# miniecu.net
KiCad netlist of a schematic drawn in EAGLE
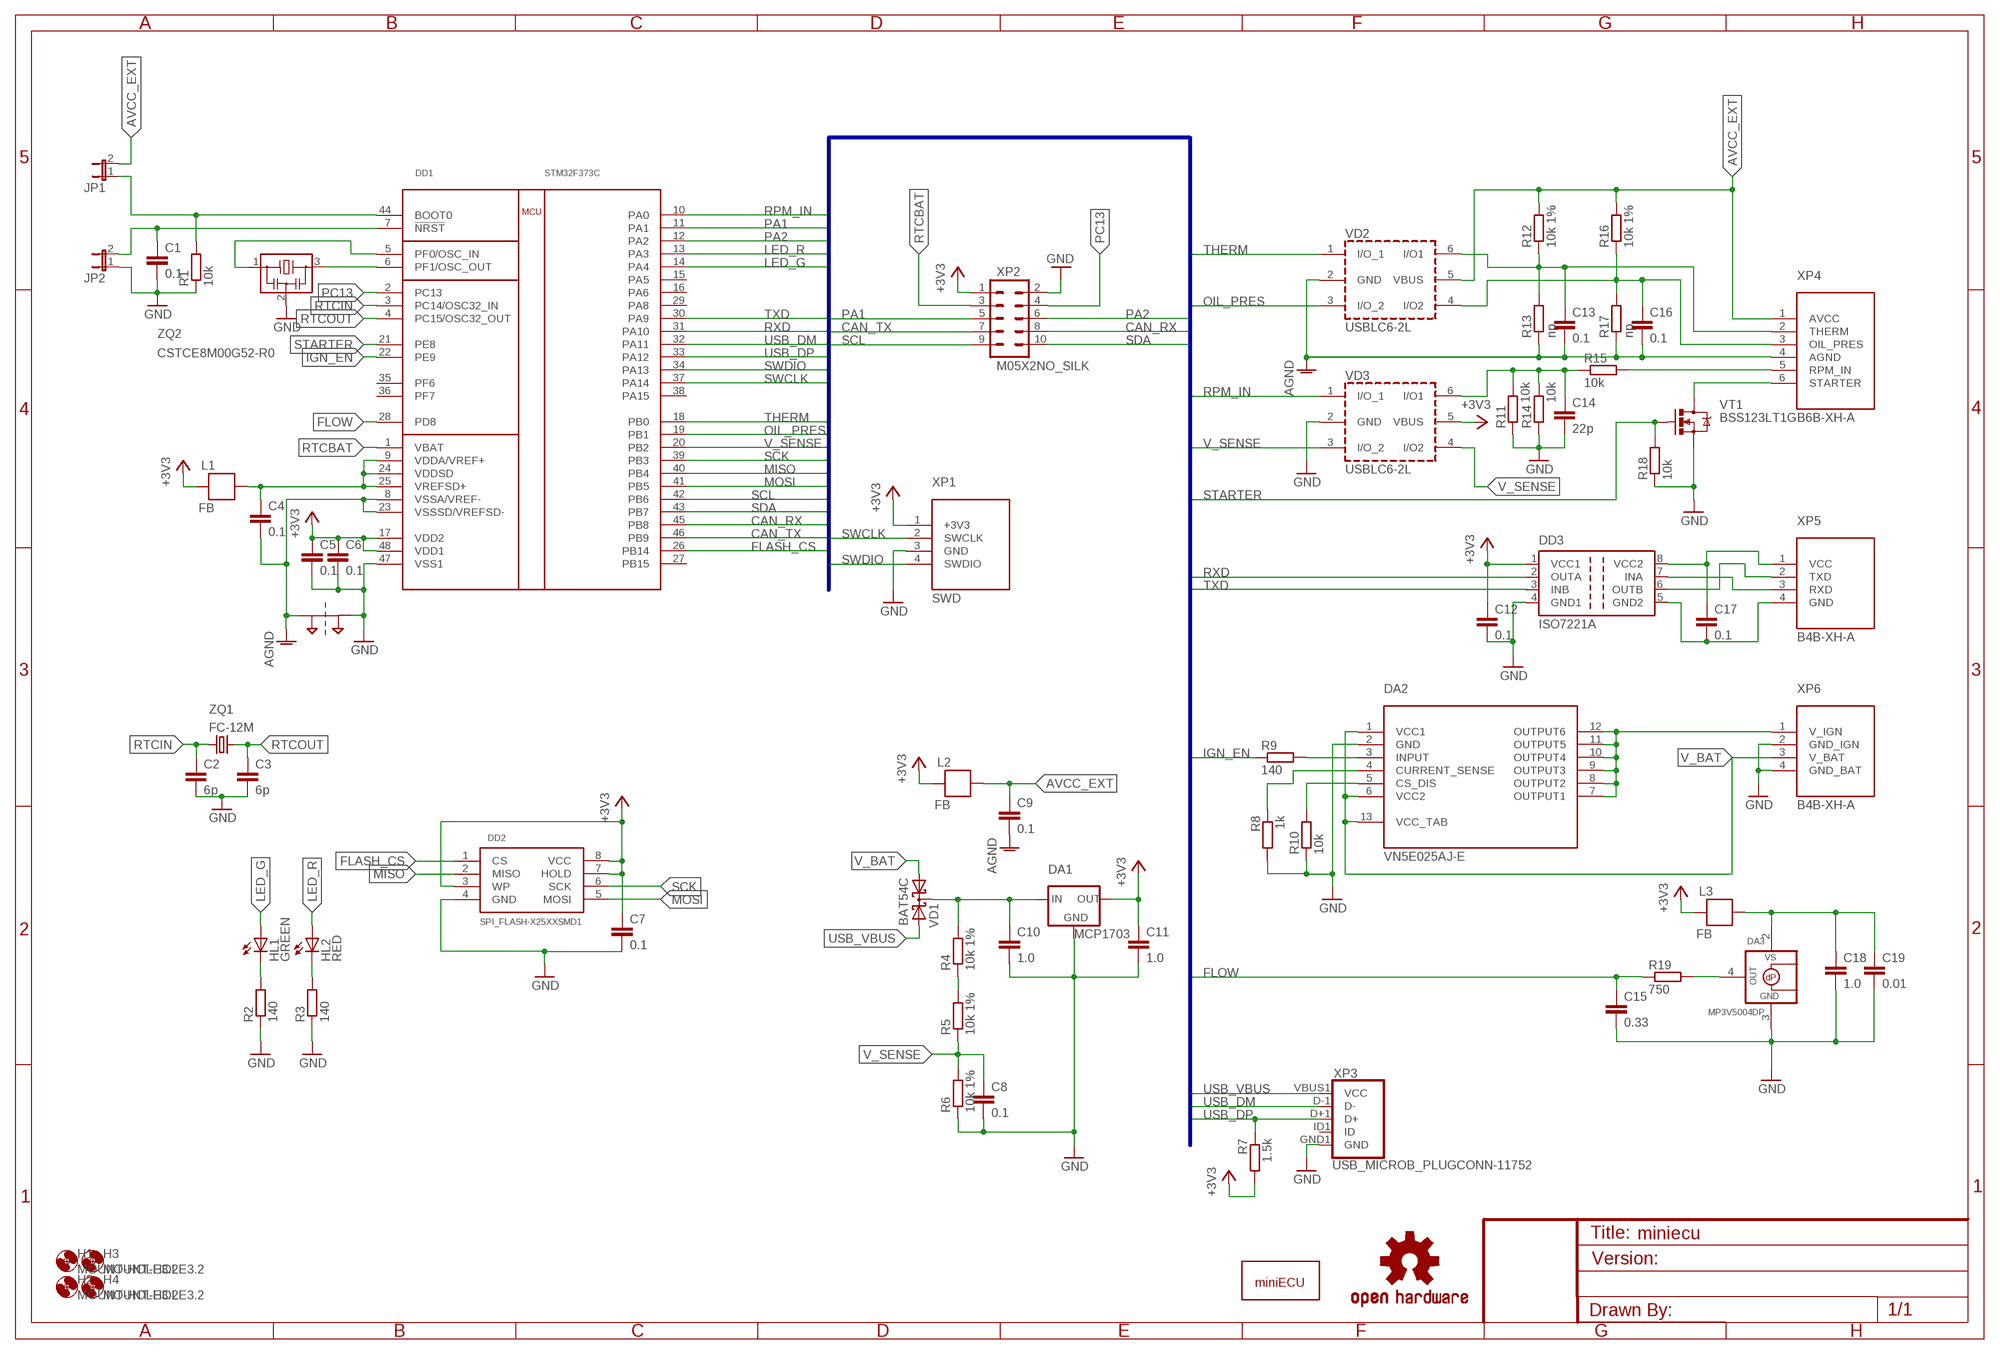
[diagram p0: schematic, sheet 1]

(export (version "E")
  (design (tool "Eeschema 10.0.6"))
  (components
    (comp (ref "C1")
      (value "0.1")
      (footprint "eagle-import:C0603")
      (libsource (lib "eagle-import") (part "C-EUC0603"))
    )
    (comp (ref "C2")
      (value "6p")
      (footprint "eagle-import:C0603")
      (libsource (lib "eagle-import") (part "C-EUC0603"))
    )
    (comp (ref "C3")
      (value "6p")
      (footprint "eagle-import:C0603")
      (libsource (lib "eagle-import") (part "C-EUC0603"))
    )
    (comp (ref "C4")
      (value "0.1")
      (footprint "eagle-import:C0603")
      (libsource (lib "eagle-import") (part "C-EUC0603"))
    )
    (comp (ref "C5")
      (value "0.1")
      (footprint "eagle-import:C0603")
      (libsource (lib "eagle-import") (part "C-EUC0603"))
    )
    (comp (ref "C6")
      (value "0.1")
      (footprint "eagle-import:C0603")
      (libsource (lib "eagle-import") (part "C-EUC0603"))
    )
    (comp (ref "C7")
      (value "0.1")
      (footprint "eagle-import:C0603")
      (libsource (lib "eagle-import") (part "C-EUC0603"))
    )
    (comp (ref "C8")
      (value "0.1")
      (footprint "eagle-import:C0603")
      (libsource (lib "eagle-import") (part "C-EUC0603"))
    )
    (comp (ref "C9")
      (value "0.1")
      (footprint "eagle-import:C0603")
      (libsource (lib "eagle-import") (part "C-EUC0603"))
    )
    (comp (ref "C10")
      (value "1.0")
      (footprint "eagle-import:C0805")
      (libsource (lib "eagle-import") (part "C-EUC0805"))
    )
    (comp (ref "C11")
      (value "1.0")
      (footprint "eagle-import:C0805")
      (libsource (lib "eagle-import") (part "C-EUC0805"))
    )
    (comp (ref "C12")
      (value "0.1")
      (footprint "eagle-import:C0603")
      (libsource (lib "eagle-import") (part "C-EUC0603"))
    )
    (comp (ref "C13")
      (value "0.1")
      (footprint "eagle-import:C0603")
      (libsource (lib "eagle-import") (part "C-EUC0603"))
    )
    (comp (ref "C14")
      (value "22p")
      (footprint "eagle-import:C0603")
      (libsource (lib "eagle-import") (part "C-EUC0603"))
    )
    (comp (ref "C15")
      (value "0.33")
      (footprint "eagle-import:C0603")
      (libsource (lib "eagle-import") (part "C-EUC0603"))
    )
    (comp (ref "C16")
      (value "0.1")
      (footprint "eagle-import:C0603")
      (libsource (lib "eagle-import") (part "C-EUC0603"))
    )
    (comp (ref "C17")
      (value "0.1")
      (footprint "eagle-import:C0603")
      (libsource (lib "eagle-import") (part "C-EUC0603"))
    )
    (comp (ref "C18")
      (value "1.0")
      (footprint "eagle-import:C0805")
      (libsource (lib "eagle-import") (part "C-EUC0805"))
    )
    (comp (ref "C19")
      (value "0.01")
      (footprint "eagle-import:C0603")
      (libsource (lib "eagle-import") (part "C-EUC0603"))
    )
    (comp (ref "DA1")
      (value "MCP1703")
      (footprint "eagle-import:SOT23")
      (libsource (lib "eagle-import") (part "MCP1700SOT-23"))
    )
    (comp (ref "DA2")
      (value "VN5E025AJ-E")
      (footprint "eagle-import:POWERSSO-12")
      (libsource (lib "eagle-import") (part "VN5E025AJ-E"))
    )
    (comp (ref "DA3")
      (value "MP3V5004DP")
      (footprint "eagle-import:SOP8-1351")
      (libsource (lib "eagle-import") (part "MPXV7025DP"))
    )
    (comp (ref "DD1")
      (value "STM32F373C")
      (footprint "eagle-import:LQFP48")
      (libsource (lib "eagle-import") (part "STM32F373C"))
    )
    (comp (ref "DD2")
      (value "SPI_FLASH-X25XXSMD1")
      (footprint "eagle-import:SO08-EIAJ")
      (libsource (lib "eagle-import") (part "SPI_FLASH-X25XXSMD1"))
    )
    (comp (ref "DD3")
      (value "ISO7221A")
      (footprint "eagle-import:SO-08")
      (fields (field (name "MPN") "ISO7221AD"))
      (libsource (lib "eagle-import") (part "ISO7221A"))
    )
    (comp (ref "H1")
      (value "MOUNT-HOLE3.2")
      (footprint "eagle-import:3,2")
      (libsource (lib "eagle-import") (part "MOUNT-HOLE3.2"))
    )
    (comp (ref "H2")
      (value "MOUNT-HOLE3.2")
      (footprint "eagle-import:3,2")
      (libsource (lib "eagle-import") (part "MOUNT-HOLE3.2"))
    )
    (comp (ref "H3")
      (value "MOUNT-HOLE3.2")
      (footprint "eagle-import:3,2")
      (libsource (lib "eagle-import") (part "MOUNT-HOLE3.2"))
    )
    (comp (ref "H4")
      (value "MOUNT-HOLE3.2")
      (footprint "eagle-import:3,2")
      (libsource (lib "eagle-import") (part "MOUNT-HOLE3.2"))
    )
    (comp (ref "HL1")
      (value "GREEN")
      (footprint "eagle-import:LED-0603")
      (libsource (lib "eagle-import") (part "LED-GREEN0603"))
    )
    (comp (ref "HL2")
      (value "RED")
      (footprint "eagle-import:LED-0603")
      (libsource (lib "eagle-import") (part "LED-RED0603"))
    )
    (comp (ref "JP1")
      (value "JUMPER-2SMD-NO")
      (footprint "eagle-import:SJ_2S-NO")
      (libsource (lib "eagle-import") (part "JUMPER-2SMD-NO"))
    )
    (comp (ref "JP2")
      (value "JUMPER-2SMD-NO")
      (footprint "eagle-import:SJ_2S-NO")
      (libsource (lib "eagle-import") (part "JUMPER-2SMD-NO"))
    )
    (comp (ref "L1")
      (value "FB")
      (footprint "eagle-import:0603")
      (libsource (lib "eagle-import") (part "FB"))
    )
    (comp (ref "L2")
      (value "FB")
      (footprint "eagle-import:0603")
      (libsource (lib "eagle-import") (part "FB"))
    )
    (comp (ref "L3")
      (value "FB")
      (footprint "eagle-import:0603")
      (libsource (lib "eagle-import") (part "FB"))
    )
    (comp (ref "LOGO1")
      (value "MINIECU_LOGO")
      (footprint "eagle-import:MINIECU_LOGO")
      (libsource (lib "eagle-import") (part "MINIECU_LOGO"))
    )
    (comp (ref "LOGO2")
      (value "OSHW-LOGOL")
      (footprint "eagle-import:OSHW-LOGO-L")
      (libsource (lib "eagle-import") (part "OSHW-LOGOL"))
    )
    (comp (ref "PT1")
      (value "2PT_GND_TIE")
      (footprint "eagle-import:2PT_GND_TIE")
      (libsource (lib "eagle-import") (part "2PT_GND_TIE"))
    )
    (comp (ref "R1")
      (value "10k")
      (footprint "eagle-import:R0603")
      (libsource (lib "eagle-import") (part "R-EU_R0603"))
    )
    (comp (ref "R2")
      (value "140")
      (footprint "eagle-import:R0603")
      (libsource (lib "eagle-import") (part "R-EU_R0603"))
    )
    (comp (ref "R3")
      (value "140")
      (footprint "eagle-import:R0603")
      (libsource (lib "eagle-import") (part "R-EU_R0603"))
    )
    (comp (ref "R4")
      (value "10k 1%")
      (footprint "eagle-import:R0805")
      (libsource (lib "eagle-import") (part "R-EU_R0805"))
    )
    (comp (ref "R5")
      (value "10k 1%")
      (footprint "eagle-import:R0805")
      (libsource (lib "eagle-import") (part "R-EU_R0805"))
    )
    (comp (ref "R6")
      (value "10k 1%")
      (footprint "eagle-import:R0805")
      (libsource (lib "eagle-import") (part "R-EU_R0805"))
    )
    (comp (ref "R7")
      (value "1.5k")
      (footprint "eagle-import:R0603")
      (libsource (lib "eagle-import") (part "R-EU_R0603"))
    )
    (comp (ref "R8")
      (value "1k")
      (footprint "eagle-import:R0603")
      (libsource (lib "eagle-import") (part "R-EU_R0603"))
    )
    (comp (ref "R9")
      (value "140")
      (footprint "eagle-import:R0603")
      (libsource (lib "eagle-import") (part "R-EU_R0603"))
    )
    (comp (ref "R10")
      (value "10k")
      (footprint "eagle-import:R0603")
      (libsource (lib "eagle-import") (part "R-EU_R0603"))
    )
    (comp (ref "R11")
      (value "10k")
      (footprint "eagle-import:R0603")
      (libsource (lib "eagle-import") (part "R-EU_R0603"))
    )
    (comp (ref "R12")
      (value "10k 1%")
      (footprint "eagle-import:R0805")
      (libsource (lib "eagle-import") (part "R-EU_R0805"))
    )
    (comp (ref "R13")
      (value "np")
      (footprint "eagle-import:R0805")
      (libsource (lib "eagle-import") (part "R-EU_R0805"))
    )
    (comp (ref "R14")
      (value "10k")
      (footprint "eagle-import:R0603")
      (libsource (lib "eagle-import") (part "R-EU_R0603"))
    )
    (comp (ref "R15")
      (value "10k")
      (footprint "eagle-import:R0603")
      (libsource (lib "eagle-import") (part "R-EU_R0603"))
    )
    (comp (ref "R16")
      (value "10k 1%")
      (footprint "eagle-import:R0805")
      (libsource (lib "eagle-import") (part "R-EU_R0805"))
    )
    (comp (ref "R17")
      (value "np")
      (footprint "eagle-import:R0805")
      (libsource (lib "eagle-import") (part "R-EU_R0805"))
    )
    (comp (ref "R18")
      (value "10k")
      (footprint "eagle-import:R0603")
      (libsource (lib "eagle-import") (part "R-EU_R0603"))
    )
    (comp (ref "R19")
      (value "750")
      (footprint "eagle-import:R0603")
      (libsource (lib "eagle-import") (part "R-EU_R0603"))
    )
    (comp (ref "VD1")
      (value "BAT54C")
      (footprint "eagle-import:SOT23")
      (libsource (lib "eagle-import") (part "BAT54C"))
    )
    (comp (ref "VD2")
      (value "USBLC6-2L")
      (footprint "eagle-import:SOT-23-6L")
      (libsource (lib "eagle-import") (part "USBLC6-2SC6"))
    )
    (comp (ref "VD3")
      (value "USBLC6-2L")
      (footprint "eagle-import:SOT-23-6L")
      (libsource (lib "eagle-import") (part "USBLC6-2SC6"))
    )
    (comp (ref "VT1")
      (value "BSS123LT1G")
      (footprint "eagle-import:SOT23")
      (libsource (lib "eagle-import") (part "MOSFET-NCHANNELBSS123LT1G"))
    )
    (comp (ref "XP1")
      (value "SWD")
      (footprint "eagle-import:1X04-1.27MM")
      (libsource (lib "eagle-import") (part "SWD"))
    )
    (comp (ref "XP2")
      (value "M05X2NO_SILK")
      (footprint "eagle-import:2X5_NOSILK")
      (libsource (lib "eagle-import") (part "M05X2NO_SILK"))
    )
    (comp (ref "XP3")
      (value "USB_MICROB_PLUGCONN-11752")
      (footprint "eagle-import:USB-B-MICRO-SMD_V03")
      (libsource (lib "eagle-import") (part "USB_MICROB_PLUGCONN-11752"))
    )
    (comp (ref "XP4")
      (value "B6B-XH-A")
      (footprint "eagle-import:B6B-XH")
      (libsource (lib "eagle-import") (part "SENSORS-B6B-XH-A"))
    )
    (comp (ref "XP5")
      (value "B4B-XH-A")
      (footprint "eagle-import:B4B-XH")
      (libsource (lib "eagle-import") (part "UART-B4B-XH-A"))
    )
    (comp (ref "XP6")
      (value "B4B-XH-A")
      (footprint "eagle-import:B4B-XH")
      (libsource (lib "eagle-import") (part "IGN_POWER-B4B-XH-A"))
    )
    (comp (ref "ZQ1")
      (value "FC-12M")
      (footprint "eagle-import:FC-12M")
      (libsource (lib "eagle-import") (part "FC-12M"))
    )
    (comp (ref "ZQ2")
      (value "CSTCE8M00G52-R0")
      (footprint "eagle-import:CSTCE")
      (libsource (lib "eagle-import") (part "CSTC?E8M00G52-R0"))
    )
  )
  (nets
    (net (code "1") (name "+3V3") (class "Default")
      (node (ref "C11") (pin "1") (pinfunction "1_1") (pintype "passive"))
      (node (ref "C12") (pin "1") (pinfunction "1_1") (pintype "passive"))
      (node (ref "C5") (pin "1") (pinfunction "1_1") (pintype "passive"))
      (node (ref "C6") (pin "1") (pinfunction "1_1") (pintype "passive"))
      (node (ref "C7") (pin "1") (pinfunction "1_1") (pintype "passive"))
      (node (ref "DA1") (pin "2") (pinfunction "OUT_2") (pintype "passive"))
      (node (ref "DD1") (pin "17") (pinfunction "VDD2_17") (pintype "power_in"))
      (node (ref "DD1") (pin "48") (pinfunction "VDD1_48") (pintype "power_in"))
      (node (ref "DD2") (pin "3") (pinfunction "WP_3") (pintype "bidirectional"))
      (node (ref "DD2") (pin "7") (pinfunction "HOLD_7") (pintype "bidirectional"))
      (node (ref "DD2") (pin "8") (pinfunction "VCC_8") (pintype "bidirectional"))
      (node (ref "DD3") (pin "1") (pinfunction "VCC1_1") (pintype "power_in"))
      (node (ref "L1") (pin "2") (pinfunction "P$2_2") (pintype "bidirectional"))
      (node (ref "L2") (pin "2") (pinfunction "P$2_2") (pintype "bidirectional"))
      (node (ref "L3") (pin "2") (pinfunction "P$2_2") (pintype "bidirectional"))
      (node (ref "R7") (pin "2") (pinfunction "2_2") (pintype "passive"))
      (node (ref "VD3") (pin "5") (pinfunction "VBUS_5") (pintype "bidirectional"))
      (node (ref "XP1") (pin "1") (pinfunction "+3V3_1") (pintype "power_in"))
      (node (ref "XP2") (pin "1") (pinfunction "1_1") (pintype "passive"))
    )
    (net (code "2") (name "/CAN_RX") (class "Default")
      (node (ref "DD1") (pin "45") (pinfunction "PB8_45") (pintype "bidirectional"))
      (node (ref "XP2") (pin "8") (pinfunction "8_8") (pintype "passive"))
    )
    (net (code "3") (name "/CAN_TX") (class "Default")
      (node (ref "DD1") (pin "46") (pinfunction "PB9_46") (pintype "bidirectional"))
      (node (ref "XP2") (pin "7") (pinfunction "7_7") (pintype "passive"))
    )
    (net (code "4") (name "/OIL_PRES") (class "Default")
      (node (ref "C16") (pin "1") (pinfunction "1_1") (pintype "passive"))
      (node (ref "DD1") (pin "19") (pinfunction "PB1_19") (pintype "bidirectional"))
      (node (ref "R16") (pin "1") (pinfunction "1_1") (pintype "passive"))
      (node (ref "R17") (pin "2") (pinfunction "2_2") (pintype "passive"))
      (node (ref "VD2") (pin "3") (pinfunction "I/O_2_3") (pintype "bidirectional"))
      (node (ref "VD2") (pin "4") (pinfunction "I/O2_4") (pintype "bidirectional"))
      (node (ref "XP4") (pin "3") (pinfunction "OIL_PRES_3") (pintype "passive"))
    )
    (net (code "5") (name "/PA1") (class "Default")
      (node (ref "DD1") (pin "11") (pinfunction "PA1_11") (pintype "bidirectional"))
      (node (ref "XP2") (pin "5") (pinfunction "5_5") (pintype "passive"))
    )
    (net (code "6") (name "/PA2") (class "Default")
      (node (ref "DD1") (pin "12") (pinfunction "PA2_12") (pintype "bidirectional"))
      (node (ref "XP2") (pin "6") (pinfunction "6_6") (pintype "passive"))
    )
    (net (code "7") (name "/RPM_IN") (class "Default")
      (node (ref "C14") (pin "1") (pinfunction "1_1") (pintype "passive"))
      (node (ref "DD1") (pin "10") (pinfunction "PA0_10") (pintype "bidirectional"))
      (node (ref "R11") (pin "2") (pinfunction "2_2") (pintype "passive"))
      (node (ref "R14") (pin "2") (pinfunction "2_2") (pintype "passive"))
      (node (ref "R15") (pin "1") (pinfunction "1_1") (pintype "passive"))
      (node (ref "VD3") (pin "1") (pinfunction "I/O_1_1") (pintype "bidirectional"))
      (node (ref "VD3") (pin "6") (pinfunction "I/O1_6") (pintype "bidirectional"))
    )
    (net (code "8") (name "/RXD") (class "Default")
      (node (ref "DD1") (pin "31") (pinfunction "PA10_31") (pintype "bidirectional"))
      (node (ref "DD3") (pin "2") (pinfunction "OUTA_2") (pintype "output"))
    )
    (net (code "9") (name "/SCL") (class "Default")
      (node (ref "DD1") (pin "42") (pinfunction "PB6_42") (pintype "bidirectional"))
      (node (ref "XP2") (pin "9") (pinfunction "9_9") (pintype "passive"))
    )
    (net (code "10") (name "/SDA") (class "Default")
      (node (ref "DD1") (pin "43") (pinfunction "PB7_43") (pintype "bidirectional"))
      (node (ref "XP2") (pin "10") (pinfunction "10_10") (pintype "passive"))
    )
    (net (code "11") (name "/SWCLK") (class "Default")
      (node (ref "DD1") (pin "37") (pinfunction "PA14_37") (pintype "bidirectional"))
      (node (ref "XP1") (pin "2") (pinfunction "SWCLK_2") (pintype "bidirectional"))
    )
    (net (code "12") (name "/SWDIO") (class "Default")
      (node (ref "DD1") (pin "34") (pinfunction "PA13_34") (pintype "bidirectional"))
      (node (ref "XP1") (pin "4") (pinfunction "SWDIO_4") (pintype "bidirectional"))
    )
    (net (code "13") (name "/THERM") (class "Default")
      (node (ref "C13") (pin "1") (pinfunction "1_1") (pintype "passive"))
      (node (ref "DD1") (pin "18") (pinfunction "PB0_18") (pintype "bidirectional"))
      (node (ref "R12") (pin "1") (pinfunction "1_1") (pintype "passive"))
      (node (ref "R13") (pin "2") (pinfunction "2_2") (pintype "passive"))
      (node (ref "VD2") (pin "1") (pinfunction "I/O_1_1") (pintype "bidirectional"))
      (node (ref "VD2") (pin "6") (pinfunction "I/O1_6") (pintype "bidirectional"))
      (node (ref "XP4") (pin "2") (pinfunction "THERM_2") (pintype "passive"))
    )
    (net (code "14") (name "/TXD") (class "Default")
      (node (ref "DD1") (pin "30") (pinfunction "PA9_30") (pintype "bidirectional"))
      (node (ref "DD3") (pin "3") (pinfunction "INB_3") (pintype "input"))
    )
    (net (code "15") (name "/USB_DM") (class "Default")
      (node (ref "DD1") (pin "32") (pinfunction "PA11_32") (pintype "bidirectional"))
      (node (ref "XP3") (pin "D-1") (pinfunction "D-_D-1") (pintype "bidirectional"))
    )
    (net (code "16") (name "/USB_DP") (class "Default")
      (node (ref "DD1") (pin "33") (pinfunction "PA12_33") (pintype "bidirectional"))
      (node (ref "R7") (pin "1") (pinfunction "1_1") (pintype "passive"))
      (node (ref "XP3") (pin "D+1") (pinfunction "D+_D+1") (pintype "bidirectional"))
    )
    (net (code "17") (name "AGND") (class "Default")
      (node (ref "C13") (pin "2") (pinfunction "2_2") (pintype "passive"))
      (node (ref "C16") (pin "2") (pinfunction "2_2") (pintype "passive"))
      (node (ref "C4") (pin "2") (pinfunction "2_2") (pintype "passive"))
      (node (ref "C9") (pin "2") (pinfunction "2_2") (pintype "passive"))
      (node (ref "DD1") (pin "23") (pinfunction "VSSSD/VREFSD-_23") (pintype "power_in"))
      (node (ref "DD1") (pin "8") (pinfunction "VSSA/VREF-_8") (pintype "power_in"))
      (node (ref "PT1") (pin "P$1") (pinfunction "P$1_P$1") (pintype "bidirectional"))
      (node (ref "R13") (pin "1") (pinfunction "1_1") (pintype "passive"))
      (node (ref "R17") (pin "1") (pinfunction "1_1") (pintype "passive"))
      (node (ref "VD2") (pin "2") (pinfunction "GND_2") (pintype "bidirectional"))
      (node (ref "XP4") (pin "4") (pinfunction "AGND_4") (pintype "passive"))
    )
    (net (code "18") (name "AVCC_EXT") (class "Default")
      (node (ref "C9") (pin "1") (pinfunction "1_1") (pintype "passive"))
      (node (ref "JP1") (pin "2") (pinfunction "2_2") (pintype "passive"))
      (node (ref "L2") (pin "1") (pinfunction "P$1_1") (pintype "bidirectional"))
      (node (ref "R12") (pin "2") (pinfunction "2_2") (pintype "passive"))
      (node (ref "R16") (pin "2") (pinfunction "2_2") (pintype "passive"))
      (node (ref "VD2") (pin "5") (pinfunction "VBUS_5") (pintype "bidirectional"))
      (node (ref "XP4") (pin "1") (pinfunction "AVCC_1") (pintype "passive"))
    )
    (net (code "19") (name "FLASH_CS") (class "Default")
      (node (ref "DD1") (pin "26") (pinfunction "PB14_26") (pintype "bidirectional"))
      (node (ref "DD2") (pin "1") (pinfunction "CS_1") (pintype "bidirectional"))
    )
    (net (code "20") (name "FLOW") (class "Default")
      (node (ref "C15") (pin "1") (pinfunction "1_1") (pintype "passive"))
      (node (ref "DD1") (pin "28") (pinfunction "PD8_28") (pintype "bidirectional"))
      (node (ref "R19") (pin "1") (pinfunction "1_1") (pintype "passive"))
    )
    (net (code "21") (name "GND") (class "Default")
      (node (ref "C1") (pin "2") (pinfunction "2_2") (pintype "passive"))
      (node (ref "C10") (pin "2") (pinfunction "2_2") (pintype "passive"))
      (node (ref "C11") (pin "2") (pinfunction "2_2") (pintype "passive"))
      (node (ref "C12") (pin "2") (pinfunction "2_2") (pintype "passive"))
      (node (ref "C14") (pin "2") (pinfunction "2_2") (pintype "passive"))
      (node (ref "C15") (pin "2") (pinfunction "2_2") (pintype "passive"))
      (node (ref "C18") (pin "2") (pinfunction "2_2") (pintype "passive"))
      (node (ref "C19") (pin "2") (pinfunction "2_2") (pintype "passive"))
      (node (ref "C2") (pin "2") (pinfunction "2_2") (pintype "passive"))
      (node (ref "C3") (pin "2") (pinfunction "2_2") (pintype "passive"))
      (node (ref "C5") (pin "2") (pinfunction "2_2") (pintype "passive"))
      (node (ref "C6") (pin "2") (pinfunction "2_2") (pintype "passive"))
      (node (ref "C7") (pin "2") (pinfunction "2_2") (pintype "passive"))
      (node (ref "C8") (pin "2") (pinfunction "2_2") (pintype "passive"))
      (node (ref "DA1") (pin "1") (pinfunction "GND_1") (pintype "input"))
      (node (ref "DA2") (pin "2") (pinfunction "GND_2") (pintype "power_in"))
      (node (ref "DA3") (pin "3") (pinfunction "GND_3") (pintype "power_in"))
      (node (ref "DD1") (pin "47") (pinfunction "VSS1_47") (pintype "power_in"))
      (node (ref "DD2") (pin "4") (pinfunction "GND_4") (pintype "bidirectional"))
      (node (ref "DD3") (pin "4") (pinfunction "GND1_4") (pintype "power_in"))
      (node (ref "JP2") (pin "1") (pinfunction "1_1") (pintype "passive"))
      (node (ref "PT1") (pin "P$2") (pinfunction "P$2_P$2") (pintype "bidirectional"))
      (node (ref "R1") (pin "1") (pinfunction "1_1") (pintype "passive"))
      (node (ref "R10") (pin "1") (pinfunction "1_1") (pintype "passive"))
      (node (ref "R11") (pin "1") (pinfunction "1_1") (pintype "passive"))
      (node (ref "R14") (pin "1") (pinfunction "1_1") (pintype "passive"))
      (node (ref "R18") (pin "1") (pinfunction "1_1") (pintype "passive"))
      (node (ref "R2") (pin "1") (pinfunction "1_1") (pintype "passive"))
      (node (ref "R3") (pin "1") (pinfunction "1_1") (pintype "passive"))
      (node (ref "R6") (pin "1") (pinfunction "1_1") (pintype "passive"))
      (node (ref "R8") (pin "2") (pinfunction "2_2") (pintype "passive"))
      (node (ref "VD3") (pin "2") (pinfunction "GND_2") (pintype "bidirectional"))
      (node (ref "VT1") (pin "2") (pinfunction "S_2") (pintype "passive"))
      (node (ref "XP1") (pin "3") (pinfunction "GND_3") (pintype "power_in"))
      (node (ref "XP2") (pin "2") (pinfunction "2_2") (pintype "passive"))
      (node (ref "XP3") (pin "GND1") (pinfunction "GND_GND1") (pintype "bidirectional"))
      (node (ref "XP6") (pin "2") (pinfunction "GND_IGN_2") (pintype "passive"))
      (node (ref "XP6") (pin "4") (pinfunction "GND_BAT_4") (pintype "passive"))
      (node (ref "ZQ2") (pin "2") (pinfunction "2_2") (pintype "passive"))
    )
    (net (code "22") (name "IGN_EN") (class "Default")
      (node (ref "DD1") (pin "22") (pinfunction "PE9_22") (pintype "bidirectional"))
      (node (ref "R9") (pin "1") (pinfunction "1_1") (pintype "passive"))
    )
    (net (code "23") (name "LED_G") (class "Default")
      (node (ref "DD1") (pin "14") (pinfunction "PA4_14") (pintype "bidirectional"))
      (node (ref "HL1") (pin "A") (pinfunction "A_A") (pintype "passive"))
    )
    (net (code "24") (name "LED_R") (class "Default")
      (node (ref "DD1") (pin "13") (pinfunction "PA3_13") (pintype "bidirectional"))
      (node (ref "HL2") (pin "A") (pinfunction "A_A") (pintype "passive"))
    )
    (net (code "25") (name "MISO") (class "Default")
      (node (ref "DD1") (pin "40") (pinfunction "PB4_40") (pintype "bidirectional"))
      (node (ref "DD2") (pin "2") (pinfunction "MISO_2") (pintype "bidirectional"))
    )
    (net (code "26") (name "MOSI") (class "Default")
      (node (ref "DD1") (pin "41") (pinfunction "PB5_41") (pintype "bidirectional"))
      (node (ref "DD2") (pin "5") (pinfunction "MOSI_5") (pintype "bidirectional"))
    )
    (net (code "27") (name "Net-(DA1-IN)") (class "Default")
      (node (ref "C10") (pin "1") (pinfunction "1_1") (pintype "passive"))
      (node (ref "DA1") (pin "3") (pinfunction "IN_3") (pintype "input"))
      (node (ref "R4") (pin "2") (pinfunction "2_2") (pintype "passive"))
      (node (ref "VD1") (pin "3") (pinfunction "CC_3") (pintype "passive"))
    )
    (net (code "28") (name "Net-(DA2-CS_DIS)") (class "Default")
      (node (ref "DA2") (pin "5") (pinfunction "CS_DIS_5") (pintype "input"))
      (node (ref "R10") (pin "2") (pinfunction "2_2") (pintype "passive"))
    )
    (net (code "29") (name "Net-(DA2-CURRENT_SENSE)") (class "Default")
      (node (ref "DA2") (pin "4") (pinfunction "CURRENT_SENSE_4") (pintype "bidirectional"))
      (node (ref "R8") (pin "1") (pinfunction "1_1") (pintype "passive"))
    )
    (net (code "30") (name "Net-(DA2-INPUT)") (class "Default")
      (node (ref "DA2") (pin "3") (pinfunction "INPUT_3") (pintype "input"))
      (node (ref "R9") (pin "2") (pinfunction "2_2") (pintype "passive"))
    )
    (net (code "31") (name "Net-(DA2-OUTPUT1)") (class "Default")
      (node (ref "DA2") (pin "10") (pinfunction "OUTPUT4_10") (pintype "power_in"))
      (node (ref "DA2") (pin "11") (pinfunction "OUTPUT5_11") (pintype "power_in"))
      (node (ref "DA2") (pin "12") (pinfunction "OUTPUT6_12") (pintype "power_in"))
      (node (ref "DA2") (pin "7") (pinfunction "OUTPUT1_7") (pintype "power_in"))
      (node (ref "DA2") (pin "8") (pinfunction "OUTPUT2_8") (pintype "power_in"))
      (node (ref "DA2") (pin "9") (pinfunction "OUTPUT3_9") (pintype "power_in"))
      (node (ref "XP6") (pin "1") (pinfunction "V_IGN_1") (pintype "passive"))
    )
    (net (code "32") (name "Net-(DA3-+VOUT)") (class "Default")
      (node (ref "DA3") (pin "4") (pinfunction "+VOUT_4") (pintype "output"))
      (node (ref "R19") (pin "2") (pinfunction "2_2") (pintype "passive"))
    )
    (net (code "33") (name "Net-(DA3-VS)") (class "Default")
      (node (ref "C18") (pin "1") (pinfunction "1_1") (pintype "passive"))
      (node (ref "C19") (pin "1") (pinfunction "1_1") (pintype "passive"))
      (node (ref "DA3") (pin "2") (pinfunction "VS_2") (pintype "power_in"))
      (node (ref "L3") (pin "1") (pinfunction "P$1_1") (pintype "bidirectional"))
    )
    (net (code "34") (name "Net-(DD1-BOOT0)") (class "Default")
      (node (ref "DD1") (pin "44") (pinfunction "BOOT0_44") (pintype "input"))
      (node (ref "JP1") (pin "1") (pinfunction "1_1") (pintype "passive"))
      (node (ref "R1") (pin "2") (pinfunction "2_2") (pintype "passive"))
    )
    (net (code "35") (name "Net-(DD1-PF0{slash}OSC_IN)") (class "Default")
      (node (ref "DD1") (pin "5") (pinfunction "PF0/OSC_IN_5") (pintype "bidirectional"))
      (node (ref "ZQ2") (pin "1") (pinfunction "1_1") (pintype "passive"))
    )
    (net (code "36") (name "Net-(DD1-PF1{slash}OSC_OUT)") (class "Default")
      (node (ref "DD1") (pin "6") (pinfunction "PF1/OSC_OUT_6") (pintype "bidirectional"))
      (node (ref "ZQ2") (pin "3") (pinfunction "3_3") (pintype "passive"))
    )
    (net (code "37") (name "Net-(DD1-VDDA{slash}VREF+)") (class "Default")
      (node (ref "C4") (pin "1") (pinfunction "1_1") (pintype "passive"))
      (node (ref "DD1") (pin "24") (pinfunction "VDDSD_24") (pintype "power_in"))
      (node (ref "DD1") (pin "25") (pinfunction "VREFSD+_25") (pintype "power_in"))
      (node (ref "DD1") (pin "9") (pinfunction "VDDA/VREF+_9") (pintype "power_in"))
      (node (ref "L1") (pin "1") (pinfunction "P$1_1") (pintype "bidirectional"))
    )
    (net (code "38") (name "Net-(DD1-~{NRST})") (class "Default")
      (node (ref "C1") (pin "1") (pinfunction "1_1") (pintype "passive"))
      (node (ref "DD1") (pin "7") (pinfunction "~{NRST}_7") (pintype "input"))
      (node (ref "JP2") (pin "2") (pinfunction "2_2") (pintype "passive"))
    )
    (net (code "39") (name "Net-(DD3-GND2)") (class "Default")
      (node (ref "C17") (pin "2") (pinfunction "2_2") (pintype "passive"))
      (node (ref "DD3") (pin "5") (pinfunction "GND2_5") (pintype "power_in"))
      (node (ref "XP5") (pin "4") (pinfunction "GND_4") (pintype "passive"))
    )
    (net (code "40") (name "Net-(DD3-INA)") (class "Default")
      (node (ref "DD3") (pin "7") (pinfunction "INA_7") (pintype "input"))
      (node (ref "XP5") (pin "3") (pinfunction "RXD_3") (pintype "passive"))
    )
    (net (code "41") (name "Net-(DD3-OUTB)") (class "Default")
      (node (ref "DD3") (pin "6") (pinfunction "OUTB_6") (pintype "output"))
      (node (ref "XP5") (pin "2") (pinfunction "TXD_2") (pintype "passive"))
    )
    (net (code "42") (name "Net-(DD3-VCC2)") (class "Default")
      (node (ref "C17") (pin "1") (pinfunction "1_1") (pintype "passive"))
      (node (ref "DD3") (pin "8") (pinfunction "VCC2_8") (pintype "power_in"))
      (node (ref "XP5") (pin "1") (pinfunction "VCC_1") (pintype "passive"))
    )
    (net (code "43") (name "Net-(HL1-PadC)") (class "Default")
      (node (ref "HL1") (pin "C") (pinfunction "C_C") (pintype "passive"))
      (node (ref "R2") (pin "2") (pinfunction "2_2") (pintype "passive"))
    )
    (net (code "44") (name "Net-(HL2-PadC)") (class "Default")
      (node (ref "HL2") (pin "C") (pinfunction "C_C") (pintype "passive"))
      (node (ref "R3") (pin "2") (pinfunction "2_2") (pintype "passive"))
    )
    (net (code "45") (name "Net-(R4-Pad1)") (class "Default")
      (node (ref "R4") (pin "1") (pinfunction "1_1") (pintype "passive"))
      (node (ref "R5") (pin "2") (pinfunction "2_2") (pintype "passive"))
    )
    (net (code "46") (name "Net-(VT1-D)") (class "Default")
      (node (ref "VT1") (pin "3") (pinfunction "D_3") (pintype "passive"))
      (node (ref "XP4") (pin "6") (pinfunction "STARTER_6") (pintype "passive"))
    )
    (net (code "47") (name "Net-(XP4-RPM_IN)") (class "Default")
      (node (ref "R15") (pin "2") (pinfunction "2_2") (pintype "passive"))
      (node (ref "XP4") (pin "5") (pinfunction "RPM_IN_5") (pintype "passive"))
    )
    (net (code "48") (name "PC13") (class "Default")
      (node (ref "DD1") (pin "2") (pinfunction "PC13_2") (pintype "bidirectional"))
      (node (ref "XP2") (pin "4") (pinfunction "4_4") (pintype "passive"))
    )
    (net (code "49") (name "RTCBAT") (class "Default")
      (node (ref "DD1") (pin "1") (pinfunction "VBAT_1") (pintype "power_in"))
      (node (ref "XP2") (pin "3") (pinfunction "3_3") (pintype "passive"))
    )
    (net (code "50") (name "RTCIN") (class "Default")
      (node (ref "C2") (pin "1") (pinfunction "1_1") (pintype "passive"))
      (node (ref "DD1") (pin "3") (pinfunction "PC14/OSC32_IN_3") (pintype "bidirectional"))
      (node (ref "ZQ1") (pin "1") (pinfunction "1_1") (pintype "passive"))
    )
    (net (code "51") (name "RTCOUT") (class "Default")
      (node (ref "C3") (pin "1") (pinfunction "1_1") (pintype "passive"))
      (node (ref "DD1") (pin "4") (pinfunction "PC15/OSC32_OUT_4") (pintype "bidirectional"))
      (node (ref "ZQ1") (pin "2") (pinfunction "2_2") (pintype "passive"))
    )
    (net (code "52") (name "SCK") (class "Default")
      (node (ref "DD1") (pin "39") (pinfunction "PB3_39") (pintype "bidirectional"))
      (node (ref "DD2") (pin "6") (pinfunction "SCK_6") (pintype "bidirectional"))
    )
    (net (code "53") (name "STARTER") (class "Default")
      (node (ref "DD1") (pin "21") (pinfunction "PE8_21") (pintype "bidirectional"))
      (node (ref "R18") (pin "2") (pinfunction "2_2") (pintype "passive"))
      (node (ref "VT1") (pin "1") (pinfunction "G_1") (pintype "passive"))
    )
    (net (code "54") (name "USB_VBUS") (class "Default")
      (node (ref "VD1") (pin "2") (pinfunction "A2_2") (pintype "passive"))
      (node (ref "XP3") (pin "VBUS1") (pinfunction "VCC_VBUS1") (pintype "bidirectional"))
    )
    (net (code "55") (name "V_BAT") (class "Default")
      (node (ref "DA2") (pin "1") (pinfunction "VCC1_1") (pintype "power_in"))
      (node (ref "DA2") (pin "13") (pinfunction "VCC_TAB_13") (pintype "power_in"))
      (node (ref "DA2") (pin "6") (pinfunction "VCC2_6") (pintype "power_in"))
      (node (ref "VD1") (pin "1") (pinfunction "A1_1") (pintype "passive"))
      (node (ref "XP6") (pin "3") (pinfunction "V_BAT_3") (pintype "passive"))
    )
    (net (code "56") (name "V_SENSE") (class "Default")
      (node (ref "C8") (pin "1") (pinfunction "1_1") (pintype "passive"))
      (node (ref "DD1") (pin "20") (pinfunction "PB2_20") (pintype "bidirectional"))
      (node (ref "R5") (pin "1") (pinfunction "1_1") (pintype "passive"))
      (node (ref "R6") (pin "2") (pinfunction "2_2") (pintype "passive"))
      (node (ref "VD3") (pin "3") (pinfunction "I/O_2_3") (pintype "bidirectional"))
      (node (ref "VD3") (pin "4") (pinfunction "I/O2_4") (pintype "bidirectional"))
    )
    (net (code "57") (name "unconnected-(DD1-PA5-Pad15)") (class "Default")
      (node (ref "DD1") (pin "15") (pinfunction "PA5_15") (pintype "bidirectional"))
    )
    (net (code "58") (name "unconnected-(DD1-PA6-Pad16)") (class "Default")
      (node (ref "DD1") (pin "16") (pinfunction "PA6_16") (pintype "bidirectional"))
    )
    (net (code "59") (name "unconnected-(DD1-PA8-Pad29)") (class "Default")
      (node (ref "DD1") (pin "29") (pinfunction "PA8_29") (pintype "bidirectional"))
    )
    (net (code "60") (name "unconnected-(DD1-PA15-Pad38)") (class "Default")
      (node (ref "DD1") (pin "38") (pinfunction "PA15_38") (pintype "bidirectional"))
    )
    (net (code "61") (name "unconnected-(DD1-PB15-Pad27)") (class "Default")
      (node (ref "DD1") (pin "27") (pinfunction "PB15_27") (pintype "bidirectional"))
    )
    (net (code "62") (name "unconnected-(DD1-PF6-Pad35)") (class "Default")
      (node (ref "DD1") (pin "35") (pinfunction "PF6_35") (pintype "bidirectional"))
    )
    (net (code "63") (name "unconnected-(DD1-PF7-Pad36)") (class "Default")
      (node (ref "DD1") (pin "36") (pinfunction "PF7_36") (pintype "bidirectional"))
    )
    (net (code "64") (name "unconnected-(XP3-ID-PadID1)") (class "Default")
      (node (ref "XP3") (pin "ID1") (pinfunction "ID_ID1") (pintype "bidirectional"))
    )
  )
)
